# MarioCube.net
KiCad netlist of a schematic drawn in EAGLE
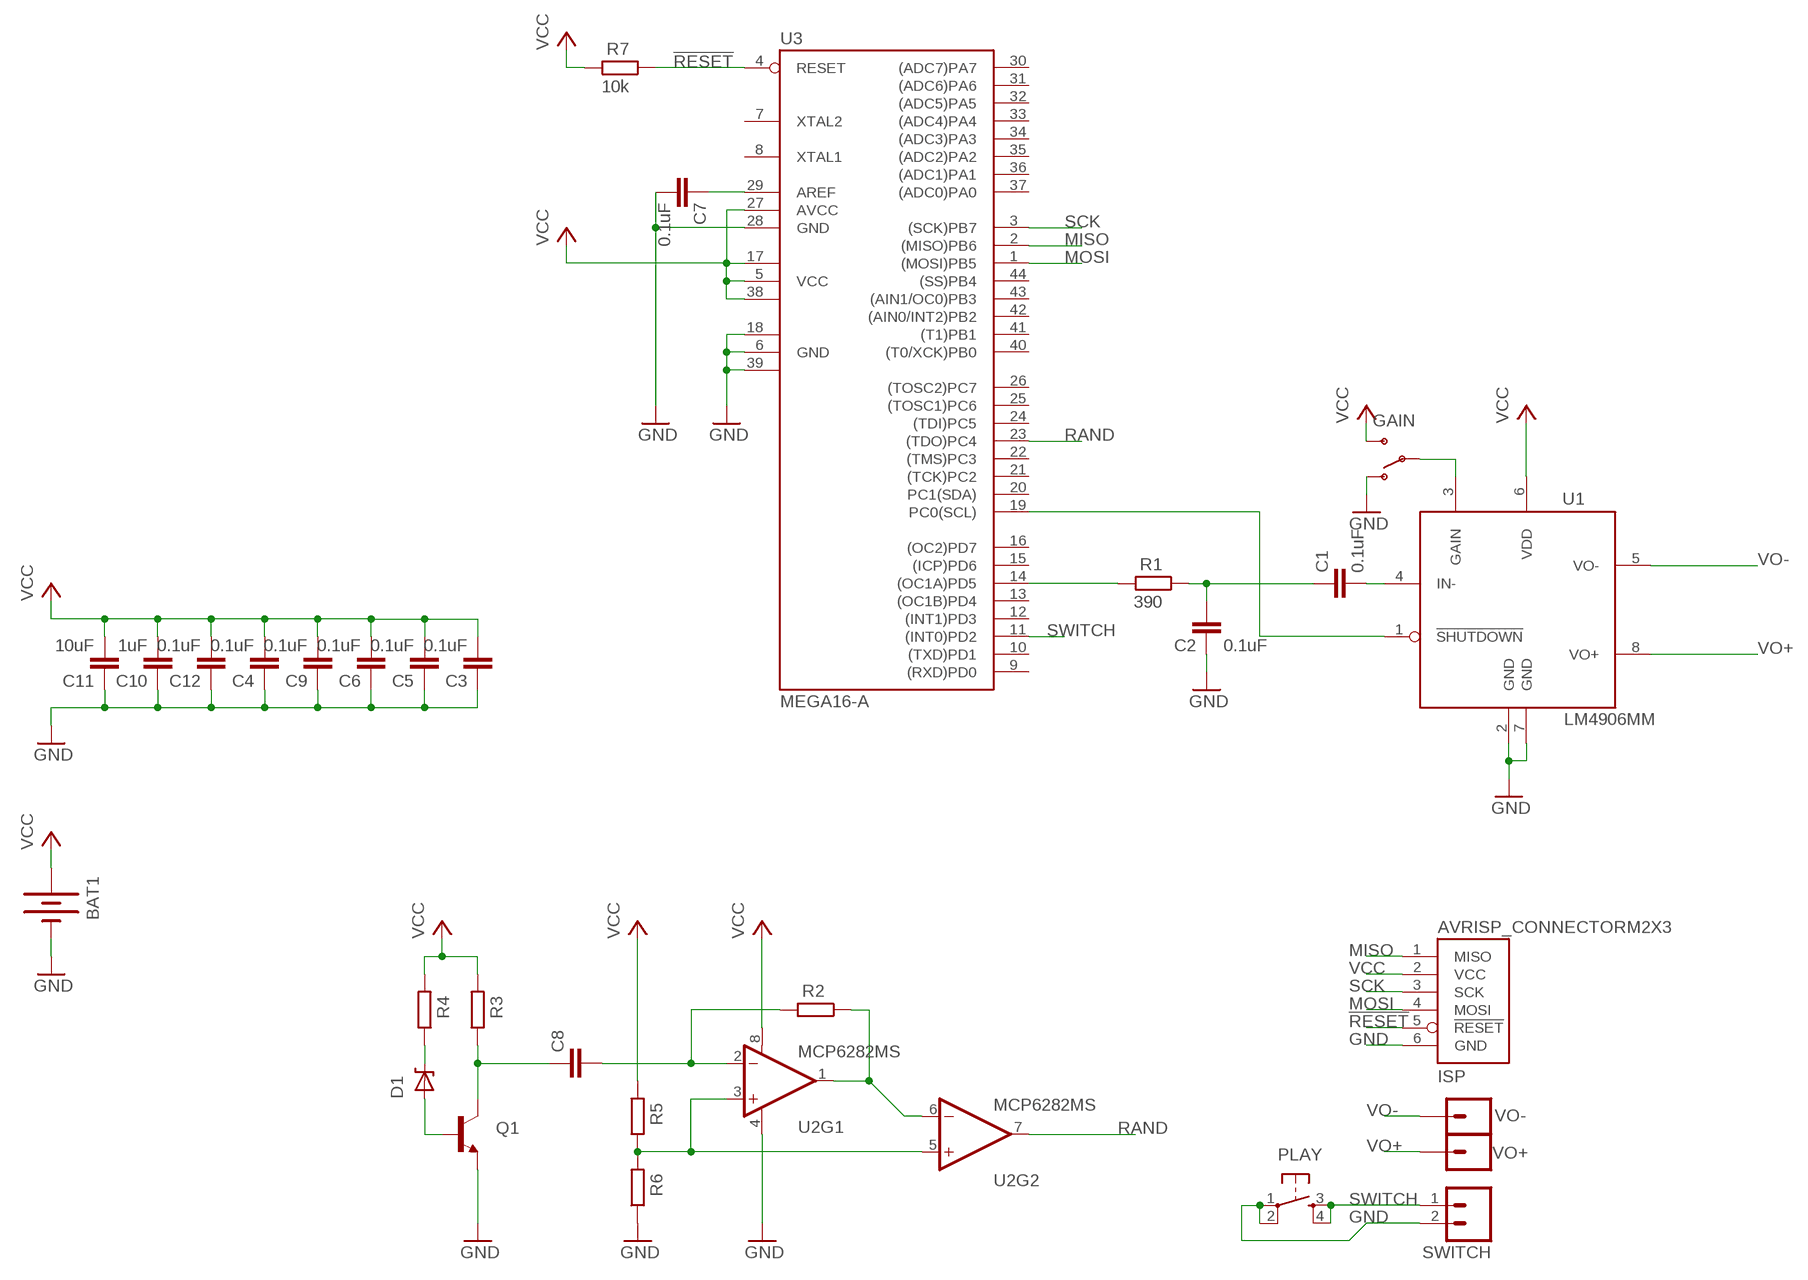
[diagram p0: schematic, sheet 1]

(export (version "E")
  (design (tool "Eeschema 10.0.6"))
  (components
    (comp (ref "BAT1")
      (value "BATTERY20MM_4LEGS")
      (footprint "eagle-import:BATTCON_20MM_4LEGS")
      (libsource (lib "eagle-import") (part "BATTERY20MM_4LEGS"))
    )
    (comp (ref "C1")
      (value "0.1uF")
      (footprint "eagle-import:C0603K")
      (libsource (lib "eagle-import") (part "C-EUC0603K"))
    )
    (comp (ref "C2")
      (value "0.1uF")
      (footprint "eagle-import:C0603K")
      (libsource (lib "eagle-import") (part "C-EUC0603K"))
    )
    (comp (ref "C3")
      (value "0.1uF")
      (footprint "eagle-import:C0603K")
      (libsource (lib "eagle-import") (part "C-EUC0603K"))
    )
    (comp (ref "C4")
      (value "0.1uF")
      (footprint "eagle-import:C0603K")
      (libsource (lib "eagle-import") (part "C-EUC0603K"))
    )
    (comp (ref "C5")
      (value "0.1uF")
      (footprint "eagle-import:C0603K")
      (libsource (lib "eagle-import") (part "C-EUC0603K"))
    )
    (comp (ref "C6")
      (value "0.1uF")
      (footprint "eagle-import:C0603K")
      (libsource (lib "eagle-import") (part "C-EUC0603K"))
    )
    (comp (ref "C7")
      (value "0.1uF")
      (footprint "eagle-import:C0603K")
      (libsource (lib "eagle-import") (part "C-EUC0603K"))
    )
    (comp (ref "C8")
      (value "C-EUC0603K")
      (footprint "eagle-import:C0603K")
      (libsource (lib "eagle-import") (part "C-EUC0603K"))
    )
    (comp (ref "C9")
      (value "0.1uF")
      (footprint "eagle-import:C0603K")
      (libsource (lib "eagle-import") (part "C-EUC0603K"))
    )
    (comp (ref "C10")
      (value "1uF")
      (footprint "eagle-import:C0805K")
      (libsource (lib "eagle-import") (part "C-EUC0805K"))
    )
    (comp (ref "C11")
      (value "10uF")
      (footprint "eagle-import:C0805K")
      (libsource (lib "eagle-import") (part "C-EUC0805K"))
    )
    (comp (ref "C12")
      (value "0.1uF")
      (footprint "eagle-import:C0603K")
      (libsource (lib "eagle-import") (part "C-EUC0603K"))
    )
    (comp (ref "D1")
      (value "DIODE-ZENERSOT23")
      (footprint "eagle-import:SOT23")
      (libsource (lib "eagle-import") (part "DIODE-ZENERSOT23"))
    )
    (comp (ref "GAIN")
      (value "SWITCH-SPSTSMD")
      (footprint "eagle-import:AYZ0202")
      (libsource (lib "eagle-import") (part "SWITCH-SPSTSMD"))
    )
    (comp (ref "ISP")
      (value "AVRISP_CONNECTORM2X3")
      (footprint "eagle-import:2X3")
      (libsource (lib "eagle-import") (part "AVRISP_CONNECTORM2X3"))
    )
    (comp (ref "PLAY")
      (value "TAC_SWITCHSMD")
      (footprint "eagle-import:TACTILE_SWITCH_SMD")
      (libsource (lib "eagle-import") (part "TAC_SWITCHSMD"))
    )
    (comp (ref "Q1")
      (value "TRANSISTOR_NPNSOT23-3")
      (footprint "eagle-import:SOT23-3")
      (libsource (lib "eagle-import") (part "TRANSISTOR_NPNSOT23-3"))
    )
    (comp (ref "R1")
      (value "390")
      (footprint "eagle-import:R0603")
      (libsource (lib "eagle-import") (part "R-EU_R0603"))
    )
    (comp (ref "R2")
      (value "R-EU_R0603")
      (footprint "eagle-import:R0603")
      (libsource (lib "eagle-import") (part "R-EU_R0603"))
    )
    (comp (ref "R3")
      (value "R-EU_R0603")
      (footprint "eagle-import:R0603")
      (libsource (lib "eagle-import") (part "R-EU_R0603"))
    )
    (comp (ref "R4")
      (value "R-EU_R0603")
      (footprint "eagle-import:R0603")
      (libsource (lib "eagle-import") (part "R-EU_R0603"))
    )
    (comp (ref "R5")
      (value "R-EU_R0603")
      (footprint "eagle-import:R0603")
      (libsource (lib "eagle-import") (part "R-EU_R0603"))
    )
    (comp (ref "R6")
      (value "R-EU_R0603")
      (footprint "eagle-import:R0603")
      (libsource (lib "eagle-import") (part "R-EU_R0603"))
    )
    (comp (ref "R7")
      (value "10k")
      (footprint "eagle-import:R0603")
      (libsource (lib "eagle-import") (part "R-EU_R0603"))
    )
    (comp (ref "SWITCH")
      (value "M02LOCK")
      (footprint "eagle-import:1X02_LOCK")
      (libsource (lib "eagle-import") (part "M02LOCK"))
    )
    (comp (ref "U1")
      (value "LM4906MM")
      (footprint "eagle-import:MSOP8")
      (libsource (lib "eagle-import") (part "LM4906MM"))
    )
    (comp (ref "U2")
      (value "MCP6282MS")
      (footprint "eagle-import:MSOP8")
      (libsource (lib "eagle-import") (part "MCP6282MS"))
    )
    (comp (ref "U3")
      (value "MEGA16-A")
      (footprint "eagle-import:TQFP44")
      (fields (field (name "MPN") "ATMEGA16-16AU"))
      (libsource (lib "eagle-import") (part "MEGA16-A"))
    )
    (comp (ref "VO+")
      (value "M01OFFSET")
      (footprint "eagle-import:1X01_OFFSET")
      (libsource (lib "eagle-import") (part "M01OFFSET"))
    )
    (comp (ref "VO-")
      (value "M01OFFSET")
      (footprint "eagle-import:1X01_OFFSET")
      (libsource (lib "eagle-import") (part "M01OFFSET"))
    )
  )
  (nets
    (net (code "1") (name "/MISO") (class "Default")
      (node (ref "ISP") (pin "1") (pinfunction "MISO_1") (pintype "bidirectional"))
      (node (ref "U3") (pin "2") (pinfunction "(MISO)PB6_2") (pintype "bidirectional"))
    )
    (net (code "2") (name "/MOSI") (class "Default")
      (node (ref "ISP") (pin "4") (pinfunction "MOSI_4") (pintype "bidirectional"))
      (node (ref "U3") (pin "1") (pinfunction "(MOSI)PB5_1") (pintype "bidirectional"))
    )
    (net (code "3") (name "/RAND") (class "Default")
      (node (ref "U2") (pin "7") (pinfunction "OUT_7") (pintype "output"))
      (node (ref "U3") (pin "23") (pinfunction "(TDO)PC4_23") (pintype "bidirectional"))
    )
    (net (code "4") (name "/SCK") (class "Default")
      (node (ref "ISP") (pin "3") (pinfunction "SCK_3") (pintype "bidirectional"))
      (node (ref "U3") (pin "3") (pinfunction "(SCK)PB7_3") (pintype "bidirectional"))
    )
    (net (code "5") (name "/SWITCH") (class "Default")
      (node (ref "PLAY") (pin "3") (pinfunction "3_3") (pintype "passive"))
      (node (ref "PLAY") (pin "4") (pinfunction "4_4") (pintype "passive"))
      (node (ref "SWITCH") (pin "1") (pinfunction "1_1") (pintype "passive"))
      (node (ref "U3") (pin "11") (pinfunction "(INT0)PD2_11") (pintype "bidirectional"))
    )
    (net (code "6") (name "/VO+") (class "Default")
      (node (ref "U1") (pin "8") (pinfunction "VO+_8") (pintype "bidirectional"))
      (node (ref "VO+") (pin "1") (pinfunction "1_1") (pintype "passive"))
    )
    (net (code "7") (name "/VO-") (class "Default")
      (node (ref "U1") (pin "5") (pinfunction "VO-_5") (pintype "bidirectional"))
      (node (ref "VO-") (pin "1") (pinfunction "1_1") (pintype "passive"))
    )
    (net (code "8") (name "/~{RESET}") (class "Default")
      (node (ref "ISP") (pin "5") (pinfunction "~{RESET}_5") (pintype "bidirectional"))
      (node (ref "R7") (pin "1") (pinfunction "1_1") (pintype "passive"))
      (node (ref "U3") (pin "4") (pinfunction "RESET_4") (pintype "input"))
    )
    (net (code "9") (name "GND") (class "Default")
      (node (ref "BAT1") (pin "2") (pinfunction "-_2") (pintype "power_in"))
      (node (ref "C10") (pin "1") (pinfunction "1_1") (pintype "passive"))
      (node (ref "C11") (pin "1") (pinfunction "1_1") (pintype "passive"))
      (node (ref "C12") (pin "1") (pinfunction "1_1") (pintype "passive"))
      (node (ref "C2") (pin "1") (pinfunction "1_1") (pintype "passive"))
      (node (ref "C3") (pin "1") (pinfunction "1_1") (pintype "passive"))
      (node (ref "C4") (pin "1") (pinfunction "1_1") (pintype "passive"))
      (node (ref "C5") (pin "1") (pinfunction "1_1") (pintype "passive"))
      (node (ref "C6") (pin "1") (pinfunction "1_1") (pintype "passive"))
      (node (ref "C7") (pin "2") (pinfunction "2_2") (pintype "passive"))
      (node (ref "C9") (pin "1") (pinfunction "1_1") (pintype "passive"))
      (node (ref "GAIN") (pin "1") (pinfunction "O_1") (pintype "passive"))
      (node (ref "ISP") (pin "6") (pinfunction "GND_6") (pintype "power_in"))
      (node (ref "PLAY") (pin "1") (pinfunction "1_1") (pintype "passive"))
      (node (ref "PLAY") (pin "2") (pinfunction "2_2") (pintype "passive"))
      (node (ref "Q1") (pin "2") (pinfunction "E_2") (pintype "passive"))
      (node (ref "R6") (pin "1") (pinfunction "1_1") (pintype "passive"))
      (node (ref "SWITCH") (pin "2") (pinfunction "2_2") (pintype "passive"))
      (node (ref "U1") (pin "2") (pinfunction "GND_2") (pintype "power_in"))
      (node (ref "U1") (pin "7") (pinfunction "GND_7") (pintype "power_in"))
      (node (ref "U2") (pin "4") (pinfunction "V-_4") (pintype "power_in"))
      (node (ref "U3") (pin "18") (pinfunction "GND1_18") (pintype "power_in"))
      (node (ref "U3") (pin "28") (pinfunction "GND_28") (pintype "power_in"))
      (node (ref "U3") (pin "39") (pinfunction "GND2_39") (pintype "power_in"))
      (node (ref "U3") (pin "6") (pinfunction "GND_6") (pintype "power_in"))
    )
    (net (code "10") (name "Net-(C1-Pad1)") (class "Default")
      (node (ref "C1") (pin "1") (pinfunction "1_1") (pintype "passive"))
      (node (ref "C2") (pin "2") (pinfunction "2_2") (pintype "passive"))
      (node (ref "R1") (pin "1") (pinfunction "1_1") (pintype "passive"))
    )
    (net (code "11") (name "Net-(D1-A)") (class "Default")
      (node (ref "D1") (pin "2") (pinfunction "A_2") (pintype "passive"))
      (node (ref "Q1") (pin "1") (pinfunction "B_1") (pintype "passive"))
    )
    (net (code "12") (name "Net-(D1-C)") (class "Default")
      (node (ref "D1") (pin "3") (pinfunction "C_3") (pintype "passive"))
      (node (ref "R4") (pin "1") (pinfunction "1_1") (pintype "passive"))
    )
    (net (code "13") (name "Net-(GAIN-P)") (class "Default")
      (node (ref "GAIN") (pin "2") (pinfunction "P_2") (pintype "passive"))
      (node (ref "U1") (pin "3") (pinfunction "GAIN_3") (pintype "bidirectional"))
    )
    (net (code "14") (name "Net-(Q1-C)") (class "Default")
      (node (ref "C8") (pin "1") (pinfunction "1_1") (pintype "passive"))
      (node (ref "Q1") (pin "3") (pinfunction "C_3") (pintype "passive"))
      (node (ref "R3") (pin "1") (pinfunction "1_1") (pintype "passive"))
    )
    (net (code "15") (name "Net-(U1-IN-)") (class "Default")
      (node (ref "C1") (pin "2") (pinfunction "2_2") (pintype "passive"))
      (node (ref "U1") (pin "4") (pinfunction "IN-_4") (pintype "bidirectional"))
    )
    (net (code "16") (name "Net-(U1-~{SHUTDOWN})") (class "Default")
      (node (ref "U1") (pin "1") (pinfunction "~{SHUTDOWN}_1") (pintype "bidirectional"))
      (node (ref "U3") (pin "19") (pinfunction "PC0(SCL)_19") (pintype "bidirectional"))
    )
    (net (code "17") (name "Net-(U2A-+IN)") (class "Default")
      (node (ref "R5") (pin "1") (pinfunction "1_1") (pintype "passive"))
      (node (ref "R6") (pin "2") (pinfunction "2_2") (pintype "passive"))
      (node (ref "U2") (pin "3") (pinfunction "+IN_3") (pintype "input"))
      (node (ref "U2") (pin "5") (pinfunction "+IN_5") (pintype "input"))
    )
    (net (code "18") (name "Net-(U2A--IN)") (class "Default")
      (node (ref "C8") (pin "2") (pinfunction "2_2") (pintype "passive"))
      (node (ref "R2") (pin "2") (pinfunction "2_2") (pintype "passive"))
      (node (ref "U2") (pin "2") (pinfunction "-IN_2") (pintype "input"))
    )
    (net (code "19") (name "Net-(U2A-OUT)") (class "Default")
      (node (ref "R2") (pin "1") (pinfunction "1_1") (pintype "passive"))
      (node (ref "U2") (pin "1") (pinfunction "OUT_1") (pintype "output"))
      (node (ref "U2") (pin "6") (pinfunction "-IN_6") (pintype "input"))
    )
    (net (code "20") (name "Net-(U3-(OC1A)PD5)") (class "Default")
      (node (ref "R1") (pin "2") (pinfunction "2_2") (pintype "passive"))
      (node (ref "U3") (pin "14") (pinfunction "(OC1A)PD5_14") (pintype "bidirectional"))
    )
    (net (code "21") (name "Net-(U3-AREF)") (class "Default")
      (node (ref "C7") (pin "1") (pinfunction "1_1") (pintype "passive"))
      (node (ref "U3") (pin "29") (pinfunction "AREF_29") (pintype "passive"))
    )
    (net (code "22") (name "VCC") (class "Default")
      (node (ref "BAT1") (pin "1") (pinfunction "+_1") (pintype "power_in"))
      (node (ref "C10") (pin "2") (pinfunction "2_2") (pintype "passive"))
      (node (ref "C11") (pin "2") (pinfunction "2_2") (pintype "passive"))
      (node (ref "C12") (pin "2") (pinfunction "2_2") (pintype "passive"))
      (node (ref "C3") (pin "2") (pinfunction "2_2") (pintype "passive"))
      (node (ref "C4") (pin "2") (pinfunction "2_2") (pintype "passive"))
      (node (ref "C5") (pin "2") (pinfunction "2_2") (pintype "passive"))
      (node (ref "C6") (pin "2") (pinfunction "2_2") (pintype "passive"))
      (node (ref "C9") (pin "2") (pinfunction "2_2") (pintype "passive"))
      (node (ref "GAIN") (pin "3") (pinfunction "S_3") (pintype "passive"))
      (node (ref "ISP") (pin "2") (pinfunction "VCC_2") (pintype "power_in"))
      (node (ref "R3") (pin "2") (pinfunction "2_2") (pintype "passive"))
      (node (ref "R4") (pin "2") (pinfunction "2_2") (pintype "passive"))
      (node (ref "R5") (pin "2") (pinfunction "2_2") (pintype "passive"))
      (node (ref "R7") (pin "2") (pinfunction "2_2") (pintype "passive"))
      (node (ref "U1") (pin "6") (pinfunction "VDD_6") (pintype "power_in"))
      (node (ref "U2") (pin "8") (pinfunction "V+_8") (pintype "power_in"))
      (node (ref "U3") (pin "17") (pinfunction "VCC1_17") (pintype "power_in"))
      (node (ref "U3") (pin "27") (pinfunction "AVCC_27") (pintype "power_in"))
      (node (ref "U3") (pin "38") (pinfunction "VCC2_38") (pintype "power_in"))
      (node (ref "U3") (pin "5") (pinfunction "VCC_5") (pintype "power_in"))
    )
    (net (code "23") (name "unconnected-(U3-(ADC0)PA0-Pad37)") (class "Default")
      (node (ref "U3") (pin "37") (pinfunction "(ADC0)PA0_37") (pintype "bidirectional"))
    )
    (net (code "24") (name "unconnected-(U3-(ADC1)PA1-Pad36)") (class "Default")
      (node (ref "U3") (pin "36") (pinfunction "(ADC1)PA1_36") (pintype "bidirectional"))
    )
    (net (code "25") (name "unconnected-(U3-(ADC2)PA2-Pad35)") (class "Default")
      (node (ref "U3") (pin "35") (pinfunction "(ADC2)PA2_35") (pintype "bidirectional"))
    )
    (net (code "26") (name "unconnected-(U3-(ADC3)PA3-Pad34)") (class "Default")
      (node (ref "U3") (pin "34") (pinfunction "(ADC3)PA3_34") (pintype "bidirectional"))
    )
    (net (code "27") (name "unconnected-(U3-(ADC4)PA4-Pad33)") (class "Default")
      (node (ref "U3") (pin "33") (pinfunction "(ADC4)PA4_33") (pintype "bidirectional"))
    )
    (net (code "28") (name "unconnected-(U3-(ADC5)PA5-Pad32)") (class "Default")
      (node (ref "U3") (pin "32") (pinfunction "(ADC5)PA5_32") (pintype "bidirectional"))
    )
    (net (code "29") (name "unconnected-(U3-(ADC6)PA6-Pad31)") (class "Default")
      (node (ref "U3") (pin "31") (pinfunction "(ADC6)PA6_31") (pintype "bidirectional"))
    )
    (net (code "30") (name "unconnected-(U3-(ADC7)PA7-Pad30)") (class "Default")
      (node (ref "U3") (pin "30") (pinfunction "(ADC7)PA7_30") (pintype "bidirectional"))
    )
    (net (code "31") (name "unconnected-(U3-(AIN0{slash}INT2)PB2-Pad42)") (class "Default")
      (node (ref "U3") (pin "42") (pinfunction "(AIN0/INT2)PB2_42") (pintype "bidirectional"))
    )
    (net (code "32") (name "unconnected-(U3-(AIN1{slash}OC0)PB3-Pad43)") (class "Default")
      (node (ref "U3") (pin "43") (pinfunction "(AIN1/OC0)PB3_43") (pintype "bidirectional"))
    )
    (net (code "33") (name "unconnected-(U3-(ICP)PD6-Pad15)") (class "Default")
      (node (ref "U3") (pin "15") (pinfunction "(ICP)PD6_15") (pintype "bidirectional"))
    )
    (net (code "34") (name "unconnected-(U3-(INT1)PD3-Pad12)") (class "Default")
      (node (ref "U3") (pin "12") (pinfunction "(INT1)PD3_12") (pintype "bidirectional"))
    )
    (net (code "35") (name "unconnected-(U3-(OC1B)PD4-Pad13)") (class "Default")
      (node (ref "U3") (pin "13") (pinfunction "(OC1B)PD4_13") (pintype "bidirectional"))
    )
    (net (code "36") (name "unconnected-(U3-(OC2)PD7-Pad16)") (class "Default")
      (node (ref "U3") (pin "16") (pinfunction "(OC2)PD7_16") (pintype "bidirectional"))
    )
    (net (code "37") (name "unconnected-(U3-(RXD)PD0-Pad9)") (class "Default")
      (node (ref "U3") (pin "9") (pinfunction "(RXD)PD0_9") (pintype "bidirectional"))
    )
    (net (code "38") (name "unconnected-(U3-(SS)PB4-Pad44)") (class "Default")
      (node (ref "U3") (pin "44") (pinfunction "(SS)PB4_44") (pintype "bidirectional"))
    )
    (net (code "39") (name "unconnected-(U3-(T0{slash}XCK)PB0-Pad40)") (class "Default")
      (node (ref "U3") (pin "40") (pinfunction "(T0/XCK)PB0_40") (pintype "bidirectional"))
    )
    (net (code "40") (name "unconnected-(U3-(T1)PB1-Pad41)") (class "Default")
      (node (ref "U3") (pin "41") (pinfunction "(T1)PB1_41") (pintype "bidirectional"))
    )
    (net (code "41") (name "unconnected-(U3-(TCK)PC2-Pad21)") (class "Default")
      (node (ref "U3") (pin "21") (pinfunction "(TCK)PC2_21") (pintype "bidirectional"))
    )
    (net (code "42") (name "unconnected-(U3-(TDI)PC5-Pad24)") (class "Default")
      (node (ref "U3") (pin "24") (pinfunction "(TDI)PC5_24") (pintype "bidirectional"))
    )
    (net (code "43") (name "unconnected-(U3-(TMS)PC3-Pad22)") (class "Default")
      (node (ref "U3") (pin "22") (pinfunction "(TMS)PC3_22") (pintype "bidirectional"))
    )
    (net (code "44") (name "unconnected-(U3-(TOSC1)PC6-Pad25)") (class "Default")
      (node (ref "U3") (pin "25") (pinfunction "(TOSC1)PC6_25") (pintype "bidirectional"))
    )
    (net (code "45") (name "unconnected-(U3-(TOSC2)PC7-Pad26)") (class "Default")
      (node (ref "U3") (pin "26") (pinfunction "(TOSC2)PC7_26") (pintype "bidirectional"))
    )
    (net (code "46") (name "unconnected-(U3-(TXD)PD1-Pad10)") (class "Default")
      (node (ref "U3") (pin "10") (pinfunction "(TXD)PD1_10") (pintype "bidirectional"))
    )
    (net (code "47") (name "unconnected-(U3-PC1(SDA)-Pad20)") (class "Default")
      (node (ref "U3") (pin "20") (pinfunction "PC1(SDA)_20") (pintype "bidirectional"))
    )
    (net (code "48") (name "unconnected-(U3-XTAL1-Pad8)") (class "Default")
      (node (ref "U3") (pin "8") (pinfunction "XTAL1_8") (pintype "bidirectional"))
    )
    (net (code "49") (name "unconnected-(U3-XTAL2-Pad7)") (class "Default")
      (node (ref "U3") (pin "7") (pinfunction "XTAL2_7") (pintype "bidirectional"))
    )
  )
)
